# IN-12Relay.net
KiCad netlist of a schematic drawn in EAGLE
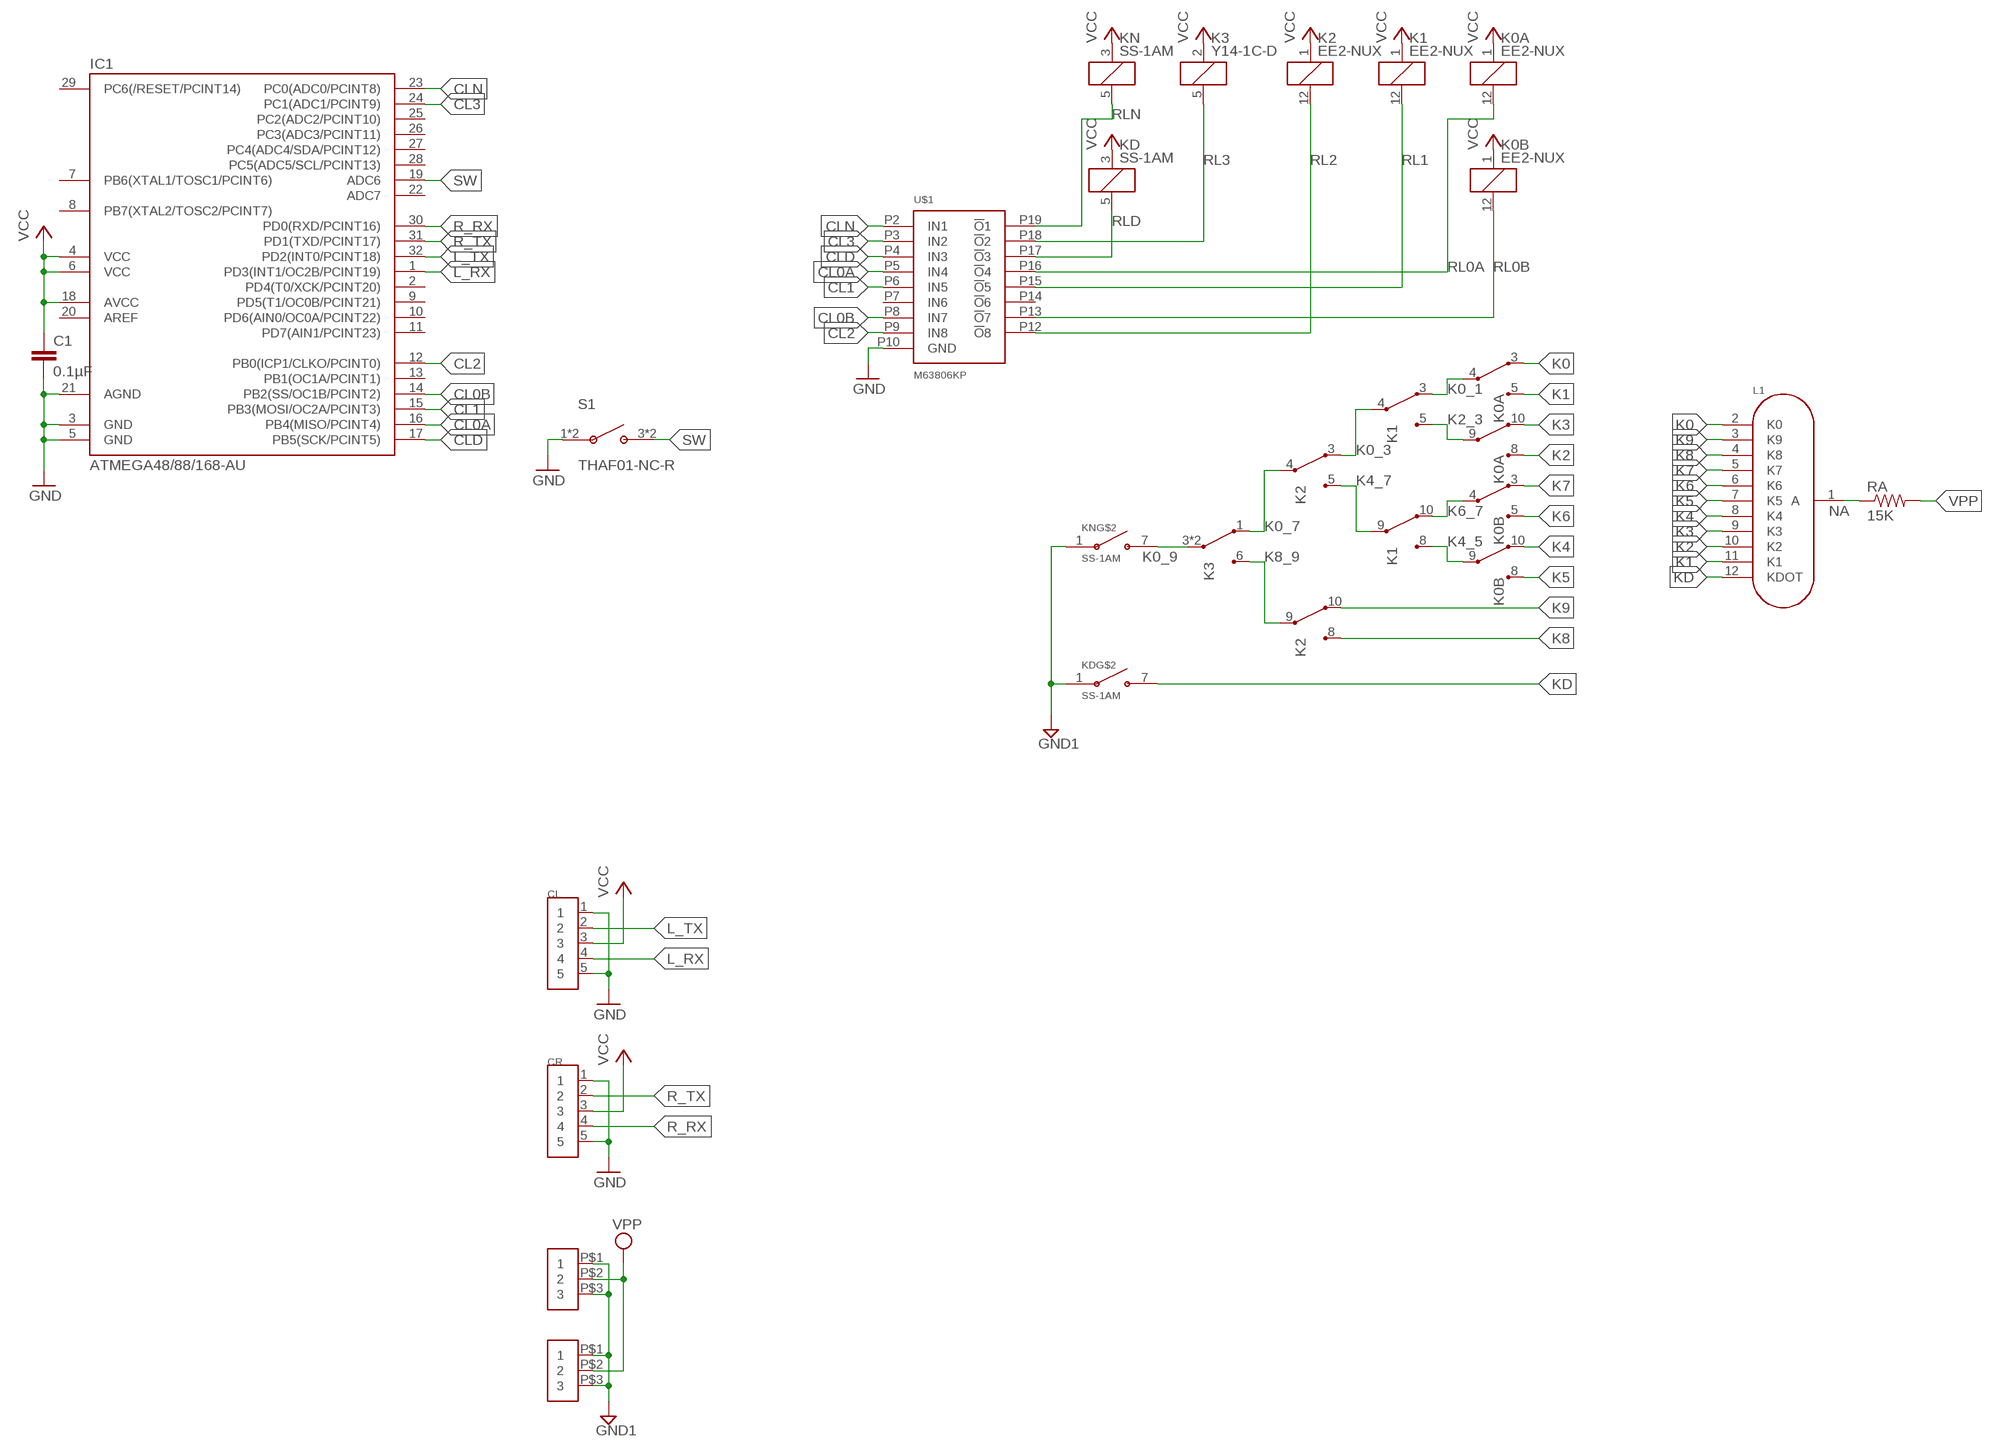
[diagram p0: schematic, sheet 1]

(export (version "E")
  (design (tool "Eeschema 10.0.6"))
  (components
    (comp (ref "C1")
      (value "0.1µF")
      (footprint "eagle-import:C0603K")
      (libsource (lib "eagle-import") (part "C-EUC0603K"))
    )
    (comp (ref "CL")
      (value "P5")
      (footprint "eagle-import:P5_2.54")
      (libsource (lib "eagle-import") (part "P5"))
    )
    (comp (ref "CR")
      (value "P5")
      (footprint "eagle-import:P5_2.54")
      (libsource (lib "eagle-import") (part "P5"))
    )
    (comp (ref "IC1")
      (value "ATMEGA48/88/168-AU")
      (footprint "eagle-import:TQFP32-08")
      (libsource (lib "eagle-import") (part "ATMEGA48/88/168-AU"))
    )
    (comp (ref "K0A")
      (value "EE2-NUX")
      (footprint "eagle-import:EE2-_NUX")
      (libsource (lib "eagle-import") (part "EE2-NUX"))
    )
    (comp (ref "K0B")
      (value "EE2-NUX")
      (footprint "eagle-import:EE2-_NUX")
      (libsource (lib "eagle-import") (part "EE2-NUX"))
    )
    (comp (ref "K1")
      (value "EE2-NUX")
      (footprint "eagle-import:EE2-_NUX")
      (libsource (lib "eagle-import") (part "EE2-NUX"))
    )
    (comp (ref "K2")
      (value "EE2-NUX")
      (footprint "eagle-import:EE2-_NUX")
      (libsource (lib "eagle-import") (part "EE2-NUX"))
    )
    (comp (ref "K3")
      (value "Y14-1C-D")
      (footprint "eagle-import:Y14_-1C-_D_")
      (libsource (lib "eagle-import") (part "Y14-1C-D"))
    )
    (comp (ref "KD")
      (value "SS-1AM")
      (footprint "eagle-import:SS-1____M")
      (libsource (lib "eagle-import") (part "SS-1AM"))
    )
    (comp (ref "KN")
      (value "SS-1AM")
      (footprint "eagle-import:SS-1____M")
      (libsource (lib "eagle-import") (part "SS-1AM"))
    )
    (comp (ref "L1")
      (value "IN-12B_PS")
      (footprint "eagle-import:IN-12_PS")
      (libsource (lib "eagle-import") (part "IN-12B_PS"))
    )
    (comp (ref "PL")
      (value "P3")
      (footprint "eagle-import:P3_2.54")
      (libsource (lib "eagle-import") (part "P3"))
    )
    (comp (ref "PR")
      (value "P3")
      (footprint "eagle-import:P3_2.54")
      (libsource (lib "eagle-import") (part "P3"))
    )
    (comp (ref "RA")
      (value "15K")
      (footprint "eagle-import:R1206")
      (libsource (lib "eagle-import") (part "R-US_R1206"))
    )
    (comp (ref "S1")
      (value "THAF01-NC-R")
      (footprint "eagle-import:THAF01-NC-R")
      (libsource (lib "eagle-import") (part "THAF01-NC-R"))
    )
    (comp (ref "U$1")
      (value "M63806KP")
      (footprint "eagle-import:20P2E")
      (libsource (lib "eagle-import") (part "M63806KP"))
    )
  )
  (nets
    (net (code "1") (name "/K0_1") (class "Default")
      (node (ref "K0A") (pin "4") (pinfunction "P_4") (pintype "passive"))
      (node (ref "K1") (pin "3") (pinfunction "S_3") (pintype "passive"))
    )
    (net (code "2") (name "/K0_3") (class "Default")
      (node (ref "K1") (pin "4") (pinfunction "P_4") (pintype "passive"))
      (node (ref "K2") (pin "3") (pinfunction "S_3") (pintype "passive"))
    )
    (net (code "3") (name "/K0_7") (class "Default")
      (node (ref "K2") (pin "4") (pinfunction "P_4") (pintype "passive"))
      (node (ref "K3") (pin "1") (pinfunction "S_1") (pintype "passive"))
    )
    (net (code "4") (name "/K0_9") (class "Default")
      (node (ref "K3") (pin "3") (pinfunction "P_3") (pintype "passive"))
      (node (ref "K3") (pin "4") (pinfunction "P_4") (pintype "passive"))
      (node (ref "KN") (pin "7") (pinfunction "P$2_7") (pintype "bidirectional"))
    )
    (net (code "5") (name "/K2_3") (class "Default")
      (node (ref "K0A") (pin "9") (pinfunction "P_9") (pintype "passive"))
      (node (ref "K1") (pin "5") (pinfunction "O_5") (pintype "passive"))
    )
    (net (code "6") (name "/K4_5") (class "Default")
      (node (ref "K0B") (pin "9") (pinfunction "P_9") (pintype "passive"))
      (node (ref "K1") (pin "8") (pinfunction "O_8") (pintype "passive"))
    )
    (net (code "7") (name "/K4_7") (class "Default")
      (node (ref "K1") (pin "9") (pinfunction "P_9") (pintype "passive"))
      (node (ref "K2") (pin "5") (pinfunction "O_5") (pintype "passive"))
    )
    (net (code "8") (name "/K6_7") (class "Default")
      (node (ref "K0B") (pin "4") (pinfunction "P_4") (pintype "passive"))
      (node (ref "K1") (pin "10") (pinfunction "S_10") (pintype "passive"))
    )
    (net (code "9") (name "/K8_9") (class "Default")
      (node (ref "K2") (pin "9") (pinfunction "P_9") (pintype "passive"))
      (node (ref "K3") (pin "6") (pinfunction "O_6") (pintype "passive"))
    )
    (net (code "10") (name "/NA") (class "Default")
      (node (ref "L1") (pin "1") (pinfunction "A_1") (pintype "bidirectional"))
      (node (ref "RA") (pin "1") (pinfunction "1_1") (pintype "passive"))
    )
    (net (code "11") (name "/RL0A") (class "Default")
      (node (ref "K0A") (pin "12") (pinfunction "2_12") (pintype "passive"))
      (node (ref "U$1") (pin "P16") (pinfunction "~{O}4_P16") (pintype "output"))
    )
    (net (code "12") (name "/RL0B") (class "Default")
      (node (ref "K0B") (pin "12") (pinfunction "2_12") (pintype "passive"))
      (node (ref "U$1") (pin "P13") (pinfunction "~{O}7_P13") (pintype "output"))
    )
    (net (code "13") (name "/RL1") (class "Default")
      (node (ref "K1") (pin "12") (pinfunction "2_12") (pintype "passive"))
      (node (ref "U$1") (pin "P15") (pinfunction "~{O}5_P15") (pintype "output"))
    )
    (net (code "14") (name "/RL2") (class "Default")
      (node (ref "K2") (pin "12") (pinfunction "2_12") (pintype "passive"))
      (node (ref "U$1") (pin "P12") (pinfunction "~{O}8_P12") (pintype "output"))
    )
    (net (code "15") (name "/RL3") (class "Default")
      (node (ref "K3") (pin "5") (pinfunction "2_5") (pintype "passive"))
      (node (ref "U$1") (pin "P18") (pinfunction "~{O}2_P18") (pintype "output"))
    )
    (net (code "16") (name "/RLD") (class "Default")
      (node (ref "KD") (pin "5") (pinfunction "2_5") (pintype "passive"))
      (node (ref "U$1") (pin "P17") (pinfunction "~{O}3_P17") (pintype "output"))
    )
    (net (code "17") (name "/RLN") (class "Default")
      (node (ref "KN") (pin "5") (pinfunction "2_5") (pintype "passive"))
      (node (ref "U$1") (pin "P19") (pinfunction "~{O}1_P19") (pintype "output"))
    )
    (net (code "18") (name "CL0A") (class "Default")
      (node (ref "IC1") (pin "16") (pinfunction "PB4(MISO/PCINT4)_16") (pintype "bidirectional"))
      (node (ref "U$1") (pin "P5") (pinfunction "IN4_P5") (pintype "input"))
    )
    (net (code "19") (name "CL0B") (class "Default")
      (node (ref "IC1") (pin "14") (pinfunction "PB2(SS/OC1B/PCINT2)_14") (pintype "bidirectional"))
      (node (ref "U$1") (pin "P8") (pinfunction "IN7_P8") (pintype "input"))
    )
    (net (code "20") (name "CL1") (class "Default")
      (node (ref "IC1") (pin "15") (pinfunction "PB3(MOSI/OC2A/PCINT3)_15") (pintype "bidirectional"))
      (node (ref "U$1") (pin "P6") (pinfunction "IN5_P6") (pintype "input"))
    )
    (net (code "21") (name "CL2") (class "Default")
      (node (ref "IC1") (pin "12") (pinfunction "PB0(ICP1/CLKO/PCINT0)_12") (pintype "bidirectional"))
      (node (ref "U$1") (pin "P9") (pinfunction "IN8_P9") (pintype "input"))
    )
    (net (code "22") (name "CL3") (class "Default")
      (node (ref "IC1") (pin "24") (pinfunction "PC1(ADC1/PCINT9)_24") (pintype "bidirectional"))
      (node (ref "U$1") (pin "P3") (pinfunction "IN2_P3") (pintype "input"))
    )
    (net (code "23") (name "CLD") (class "Default")
      (node (ref "IC1") (pin "17") (pinfunction "PB5(SCK/PCINT5)_17") (pintype "bidirectional"))
      (node (ref "U$1") (pin "P4") (pinfunction "IN3_P4") (pintype "input"))
    )
    (net (code "24") (name "CLN") (class "Default")
      (node (ref "IC1") (pin "23") (pinfunction "PC0(ADC0/PCINT8)_23") (pintype "bidirectional"))
      (node (ref "U$1") (pin "P2") (pinfunction "IN1_P2") (pintype "input"))
    )
    (net (code "25") (name "GND") (class "Default")
      (node (ref "C1") (pin "2") (pinfunction "2_2") (pintype "passive"))
      (node (ref "CL") (pin "1") (pinfunction "1_1") (pintype "bidirectional"))
      (node (ref "CL") (pin "5") (pinfunction "5_5") (pintype "bidirectional"))
      (node (ref "CR") (pin "1") (pinfunction "1_1") (pintype "bidirectional"))
      (node (ref "CR") (pin "5") (pinfunction "5_5") (pintype "bidirectional"))
      (node (ref "IC1") (pin "21") (pinfunction "AGND_21") (pintype "power_in"))
      (node (ref "IC1") (pin "3") (pinfunction "GND_3") (pintype "power_in"))
      (node (ref "IC1") (pin "5") (pinfunction "GND_5") (pintype "power_in"))
      (node (ref "S1") (pin "1") (pinfunction "A_1") (pintype "bidirectional"))
      (node (ref "S1") (pin "2") (pinfunction "A_2") (pintype "bidirectional"))
      (node (ref "U$1") (pin "P10") (pinfunction "GND_P10") (pintype "power_in"))
    )
    (net (code "26") (name "GND1") (class "Default")
      (node (ref "KD") (pin "1") (pinfunction "P$1_1") (pintype "bidirectional"))
      (node (ref "KN") (pin "1") (pinfunction "P$1_1") (pintype "bidirectional"))
      (node (ref "PL") (pin "P$1") (pinfunction "1_P$1") (pintype "bidirectional"))
      (node (ref "PL") (pin "P$3") (pinfunction "3_P$3") (pintype "bidirectional"))
      (node (ref "PR") (pin "P$1") (pinfunction "1_P$1") (pintype "bidirectional"))
      (node (ref "PR") (pin "P$3") (pinfunction "3_P$3") (pintype "bidirectional"))
    )
    (net (code "27") (name "K0") (class "Default")
      (node (ref "K0A") (pin "3") (pinfunction "S_3") (pintype "passive"))
      (node (ref "L1") (pin "2") (pinfunction "K0_2") (pintype "bidirectional"))
    )
    (net (code "28") (name "K1") (class "Default")
      (node (ref "K0A") (pin "5") (pinfunction "O_5") (pintype "passive"))
      (node (ref "L1") (pin "11") (pinfunction "K1_11") (pintype "bidirectional"))
    )
    (net (code "29") (name "K2") (class "Default")
      (node (ref "K0A") (pin "8") (pinfunction "O_8") (pintype "passive"))
      (node (ref "L1") (pin "10") (pinfunction "K2_10") (pintype "bidirectional"))
    )
    (net (code "30") (name "K3") (class "Default")
      (node (ref "K0A") (pin "10") (pinfunction "S_10") (pintype "passive"))
      (node (ref "L1") (pin "9") (pinfunction "K3_9") (pintype "bidirectional"))
    )
    (net (code "31") (name "K4") (class "Default")
      (node (ref "K0B") (pin "10") (pinfunction "S_10") (pintype "passive"))
      (node (ref "L1") (pin "8") (pinfunction "K4_8") (pintype "bidirectional"))
    )
    (net (code "32") (name "K5") (class "Default")
      (node (ref "K0B") (pin "8") (pinfunction "O_8") (pintype "passive"))
      (node (ref "L1") (pin "7") (pinfunction "K5_7") (pintype "bidirectional"))
    )
    (net (code "33") (name "K6") (class "Default")
      (node (ref "K0B") (pin "5") (pinfunction "O_5") (pintype "passive"))
      (node (ref "L1") (pin "6") (pinfunction "K6_6") (pintype "bidirectional"))
    )
    (net (code "34") (name "K7") (class "Default")
      (node (ref "K0B") (pin "3") (pinfunction "S_3") (pintype "passive"))
      (node (ref "L1") (pin "5") (pinfunction "K7_5") (pintype "bidirectional"))
    )
    (net (code "35") (name "K8") (class "Default")
      (node (ref "K2") (pin "8") (pinfunction "O_8") (pintype "passive"))
      (node (ref "L1") (pin "4") (pinfunction "K8_4") (pintype "bidirectional"))
    )
    (net (code "36") (name "K9") (class "Default")
      (node (ref "K2") (pin "10") (pinfunction "S_10") (pintype "passive"))
      (node (ref "L1") (pin "3") (pinfunction "K9_3") (pintype "bidirectional"))
    )
    (net (code "37") (name "KD") (class "Default")
      (node (ref "KD") (pin "7") (pinfunction "P$2_7") (pintype "bidirectional"))
      (node (ref "L1") (pin "12") (pinfunction "KDOT_12") (pintype "bidirectional"))
    )
    (net (code "38") (name "L_RX") (class "Default")
      (node (ref "CL") (pin "4") (pinfunction "4_4") (pintype "bidirectional"))
      (node (ref "IC1") (pin "1") (pinfunction "PD3(INT1/OC2B/PCINT19)_1") (pintype "bidirectional"))
    )
    (net (code "39") (name "L_TX") (class "Default")
      (node (ref "CL") (pin "2") (pinfunction "2_2") (pintype "bidirectional"))
      (node (ref "IC1") (pin "32") (pinfunction "PD2(INT0/PCINT18)_32") (pintype "bidirectional"))
    )
    (net (code "40") (name "R_RX") (class "Default")
      (node (ref "CR") (pin "4") (pinfunction "4_4") (pintype "bidirectional"))
      (node (ref "IC1") (pin "30") (pinfunction "PD0(RXD/PCINT16)_30") (pintype "bidirectional"))
    )
    (net (code "41") (name "R_TX") (class "Default")
      (node (ref "CR") (pin "2") (pinfunction "2_2") (pintype "bidirectional"))
      (node (ref "IC1") (pin "31") (pinfunction "PD1(TXD/PCINT17)_31") (pintype "bidirectional"))
    )
    (net (code "42") (name "SW") (class "Default")
      (node (ref "IC1") (pin "19") (pinfunction "ADC6_19") (pintype "passive"))
      (node (ref "S1") (pin "3") (pinfunction "B_3") (pintype "bidirectional"))
      (node (ref "S1") (pin "4") (pinfunction "B_4") (pintype "bidirectional"))
    )
    (net (code "43") (name "VCC") (class "Default")
      (node (ref "C1") (pin "1") (pinfunction "1_1") (pintype "passive"))
      (node (ref "CL") (pin "3") (pinfunction "3_3") (pintype "bidirectional"))
      (node (ref "CR") (pin "3") (pinfunction "3_3") (pintype "bidirectional"))
      (node (ref "IC1") (pin "18") (pinfunction "AVCC_18") (pintype "passive"))
      (node (ref "IC1") (pin "4") (pinfunction "VCC_4") (pintype "power_in"))
      (node (ref "IC1") (pin "6") (pinfunction "VCC_6") (pintype "power_in"))
      (node (ref "K0A") (pin "1") (pinfunction "1_1") (pintype "passive"))
      (node (ref "K0B") (pin "1") (pinfunction "1_1") (pintype "passive"))
      (node (ref "K1") (pin "1") (pinfunction "1_1") (pintype "passive"))
      (node (ref "K2") (pin "1") (pinfunction "1_1") (pintype "passive"))
      (node (ref "K3") (pin "2") (pinfunction "1_2") (pintype "passive"))
      (node (ref "KD") (pin "3") (pinfunction "1_3") (pintype "passive"))
      (node (ref "KN") (pin "3") (pinfunction "1_3") (pintype "passive"))
    )
    (net (code "44") (name "VPP") (class "Default")
      (node (ref "PL") (pin "P$2") (pinfunction "2_P$2") (pintype "bidirectional"))
      (node (ref "PR") (pin "P$2") (pinfunction "2_P$2") (pintype "bidirectional"))
      (node (ref "RA") (pin "2") (pinfunction "2_2") (pintype "passive"))
    )
    (net (code "45") (name "unconnected-(IC1-ADC7-Pad22)") (class "Default")
      (node (ref "IC1") (pin "22") (pinfunction "ADC7_22") (pintype "passive"))
    )
    (net (code "46") (name "unconnected-(IC1-AREF-Pad20)") (class "Default")
      (node (ref "IC1") (pin "20") (pinfunction "AREF_20") (pintype "passive"))
    )
    (net (code "47") (name "unconnected-(IC1-PB1(OC1A{slash}PCINT1)-Pad13)") (class "Default")
      (node (ref "IC1") (pin "13") (pinfunction "PB1(OC1A/PCINT1)_13") (pintype "bidirectional"))
    )
    (net (code "48") (name "unconnected-(IC1-PB6(XTAL1{slash}TOSC1{slash}PCINT6)-Pad7)") (class "Default")
      (node (ref "IC1") (pin "7") (pinfunction "PB6(XTAL1/TOSC1/PCINT6)_7") (pintype "bidirectional"))
    )
    (net (code "49") (name "unconnected-(IC1-PB7(XTAL2{slash}TOSC2{slash}PCINT7)-Pad8)") (class "Default")
      (node (ref "IC1") (pin "8") (pinfunction "PB7(XTAL2/TOSC2/PCINT7)_8") (pintype "bidirectional"))
    )
    (net (code "50") (name "unconnected-(IC1-PC2(ADC2{slash}PCINT10)-Pad25)") (class "Default")
      (node (ref "IC1") (pin "25") (pinfunction "PC2(ADC2/PCINT10)_25") (pintype "bidirectional"))
    )
    (net (code "51") (name "unconnected-(IC1-PC3(ADC3{slash}PCINT11)-Pad26)") (class "Default")
      (node (ref "IC1") (pin "26") (pinfunction "PC3(ADC3/PCINT11)_26") (pintype "bidirectional"))
    )
    (net (code "52") (name "unconnected-(IC1-PC4(ADC4{slash}SDA{slash}PCINT12)-Pad27)") (class "Default")
      (node (ref "IC1") (pin "27") (pinfunction "PC4(ADC4/SDA/PCINT12)_27") (pintype "bidirectional"))
    )
    (net (code "53") (name "unconnected-(IC1-PC5(ADC5{slash}SCL{slash}PCINT13)-Pad28)") (class "Default")
      (node (ref "IC1") (pin "28") (pinfunction "PC5(ADC5/SCL/PCINT13)_28") (pintype "bidirectional"))
    )
    (net (code "54") (name "unconnected-(IC1-PC6({slash}RESET{slash}PCINT14)-Pad29)") (class "Default")
      (node (ref "IC1") (pin "29") (pinfunction "PC6(/RESET/PCINT14)_29") (pintype "bidirectional"))
    )
    (net (code "55") (name "unconnected-(IC1-PD4(T0{slash}XCK{slash}PCINT20)-Pad2)") (class "Default")
      (node (ref "IC1") (pin "2") (pinfunction "PD4(T0/XCK/PCINT20)_2") (pintype "bidirectional"))
    )
    (net (code "56") (name "unconnected-(IC1-PD5(T1{slash}OC0B{slash}PCINT21)-Pad9)") (class "Default")
      (node (ref "IC1") (pin "9") (pinfunction "PD5(T1/OC0B/PCINT21)_9") (pintype "bidirectional"))
    )
    (net (code "57") (name "unconnected-(IC1-PD6(AIN0{slash}OC0A{slash}PCINT22)-Pad10)") (class "Default")
      (node (ref "IC1") (pin "10") (pinfunction "PD6(AIN0/OC0A/PCINT22)_10") (pintype "bidirectional"))
    )
    (net (code "58") (name "unconnected-(IC1-PD7(AIN1{slash}PCINT23)-Pad11)") (class "Default")
      (node (ref "IC1") (pin "11") (pinfunction "PD7(AIN1/PCINT23)_11") (pintype "bidirectional"))
    )
    (net (code "59") (name "unconnected-(U$1-IN6-PadP7)") (class "Default")
      (node (ref "U$1") (pin "P7") (pinfunction "IN6_P7") (pintype "input"))
    )
    (net (code "60") (name "unconnected-(U$1-~{O}6-PadP14)") (class "Default")
      (node (ref "U$1") (pin "P14") (pinfunction "~{O}6_P14") (pintype "output"))
    )
  )
)
